# Sheet2.net
KiCad netlist of a schematic drawn in Altium Designer
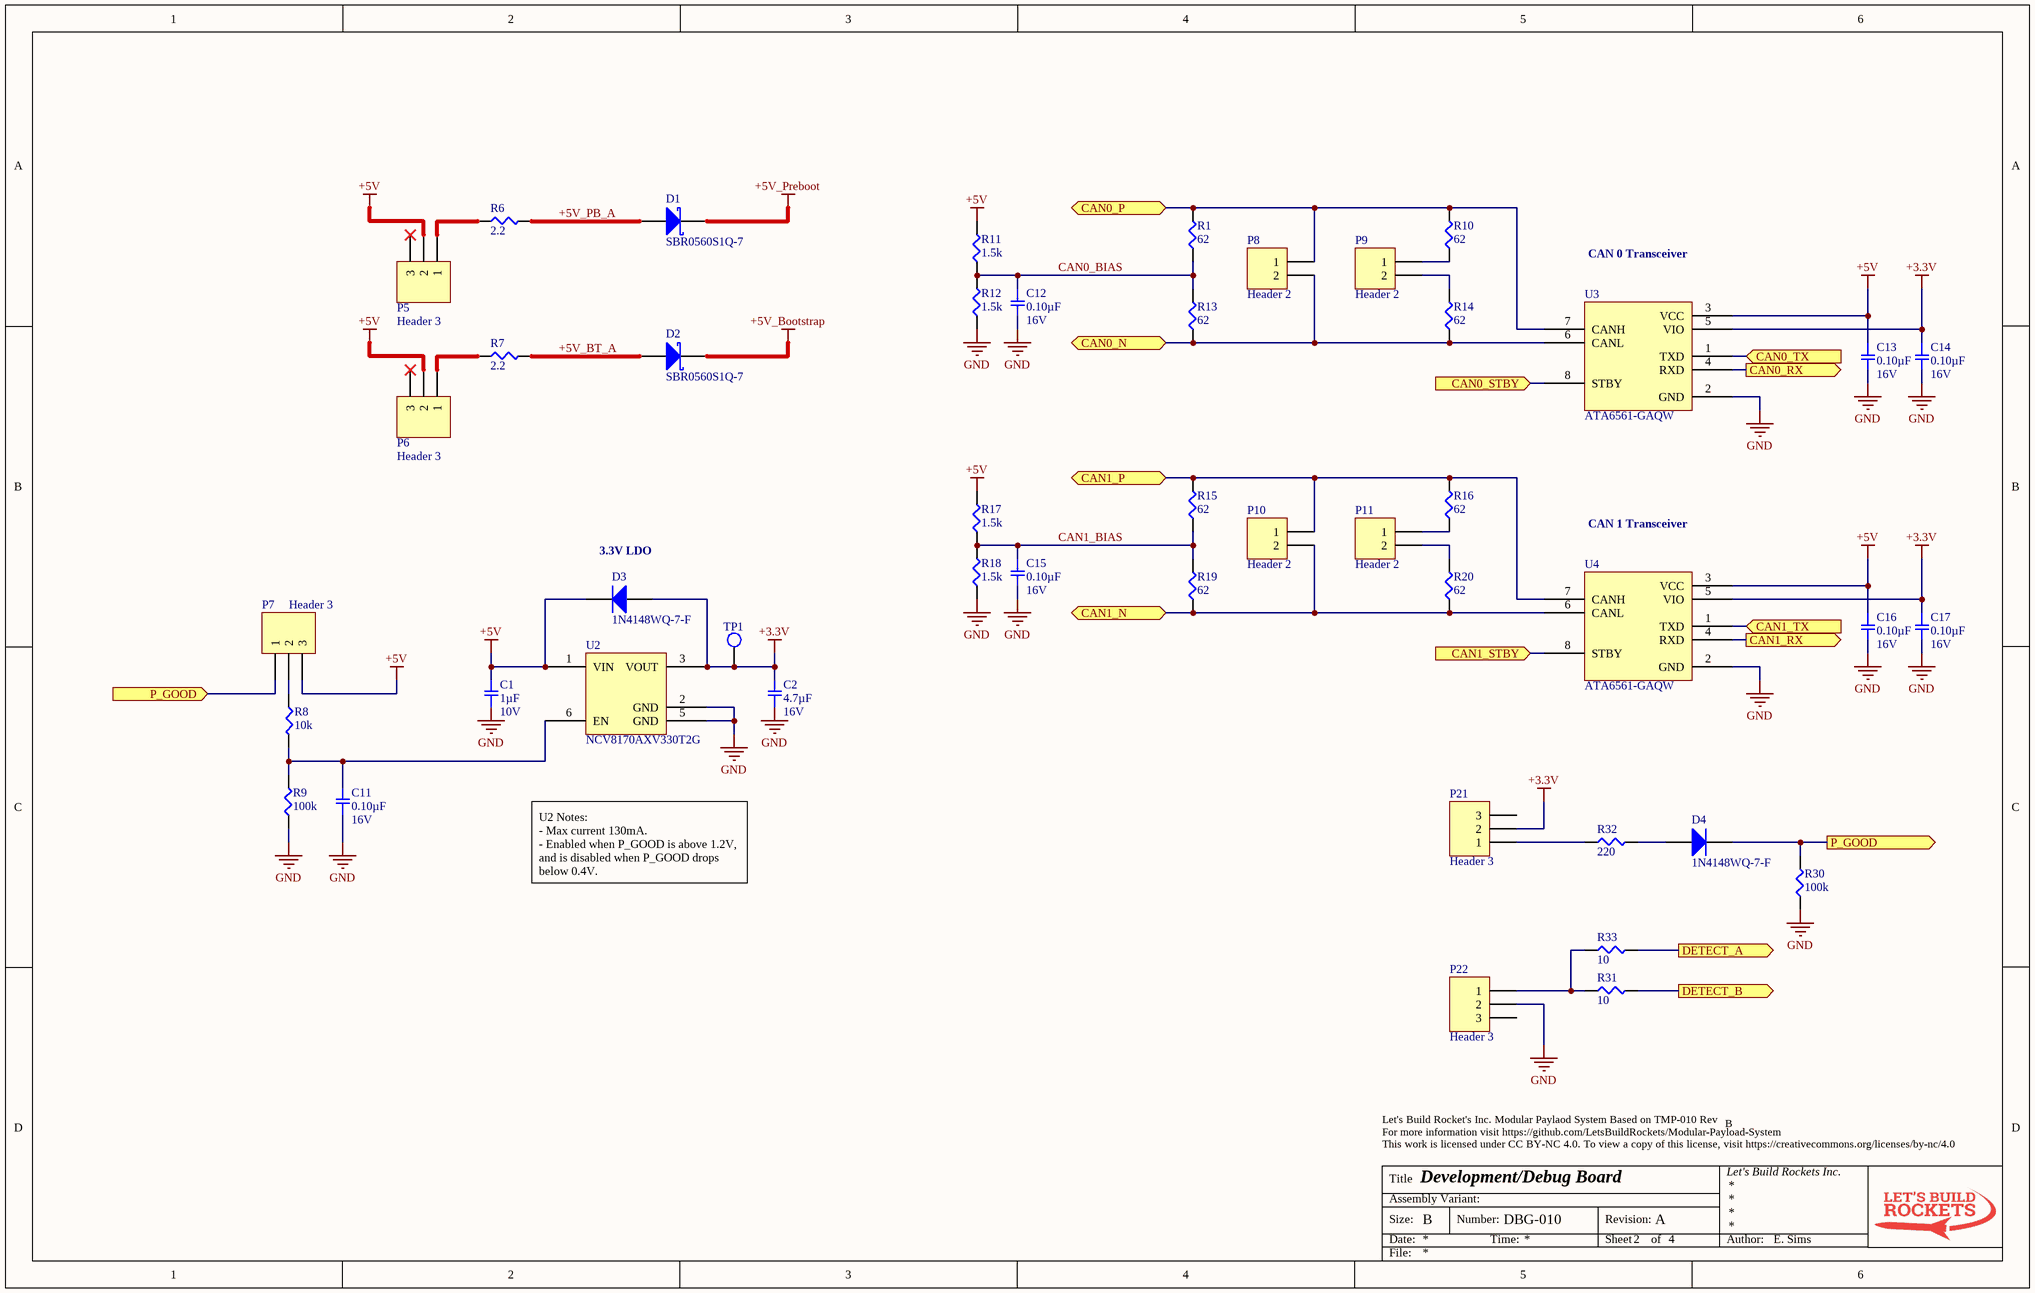
[diagram p0: Sheet2.SchDoc]

(export (version "E")
  (design (tool "Eeschema 10.0.6"))
  (components
    (comp (ref "C1")
      (value "1µF")
      (footprint "SMD-0402C")
      (description "CAP CER 1UF 10V X7S 0402")
      (fields
        (field (name "DIGI-KEY PART NUMBER") "490-13409-1-ND")
        (field (name "PART NUMBER") "GCM155C71A105KE38D")
        (field (name "VOLTAGE") "10V")
      )
      (libsource (lib "capacitor_murata_0402") (part "GCM155C71A105KE38D"))
    )
    (comp (ref "C2")
      (value "4.7µF")
      (footprint "SMD-0805C")
      (description "CAP CER 4.7UF 16V X7R 0805")
      (fields
        (field (name "DIGI-KEY PART NUMBER") "490-10557-1-ND")
        (field (name "PART NUMBER") "GCJ21BR71C475KA01L")
        (field (name "VOLTAGE") "16V")
      )
      (libsource (lib "capacitor_murata_0805") (part "GCJ21BR71C475KA01L"))
    )
    (comp (ref "C11")
      (value "0.10µF")
      (footprint "SMD-0402C")
      (description "CAP CER 0.1UF 16V X7R 0402")
      (fields
        (field (name "DIGI-KEY PART NUMBER") "490-4759-1-ND")
        (field (name "PART NUMBER") "GCM155R71C104KA55D")
        (field (name "VOLTAGE") "16V")
      )
      (libsource (lib "capacitor_murata_0402") (part "GCM155R71C104KA55D"))
    )
    (comp (ref "C12")
      (value "0.10µF")
      (footprint "SMD-0402C")
      (description "CAP CER 0.1UF 16V X7R 0402")
      (fields
        (field (name "DIGI-KEY PART NUMBER") "490-4759-1-ND")
        (field (name "PART NUMBER") "GCM155R71C104KA55D")
        (field (name "VOLTAGE") "16V")
      )
      (libsource (lib "capacitor_murata_0402") (part "GCM155R71C104KA55D"))
    )
    (comp (ref "C13")
      (value "0.10µF")
      (footprint "SMD-0402C")
      (description "CAP CER 0.1UF 16V X7R 0402")
      (fields
        (field (name "DIGI-KEY PART NUMBER") "490-4759-1-ND")
        (field (name "PART NUMBER") "GCM155R71C104KA55D")
        (field (name "VOLTAGE") "16V")
      )
      (libsource (lib "capacitor_murata_0402") (part "GCM155R71C104KA55D"))
    )
    (comp (ref "C14")
      (value "0.10µF")
      (footprint "SMD-0402C")
      (description "CAP CER 0.1UF 16V X7R 0402")
      (fields
        (field (name "DIGI-KEY PART NUMBER") "490-4759-1-ND")
        (field (name "PART NUMBER") "GCM155R71C104KA55D")
        (field (name "VOLTAGE") "16V")
      )
      (libsource (lib "capacitor_murata_0402") (part "GCM155R71C104KA55D"))
    )
    (comp (ref "C15")
      (value "0.10µF")
      (footprint "SMD-0402C")
      (description "CAP CER 0.1UF 16V X7R 0402")
      (fields
        (field (name "DIGI-KEY PART NUMBER") "490-4759-1-ND")
        (field (name "PART NUMBER") "GCM155R71C104KA55D")
        (field (name "VOLTAGE") "16V")
      )
      (libsource (lib "capacitor_murata_0402") (part "GCM155R71C104KA55D"))
    )
    (comp (ref "C16")
      (value "0.10µF")
      (footprint "SMD-0402C")
      (description "CAP CER 0.1UF 16V X7R 0402")
      (fields
        (field (name "DIGI-KEY PART NUMBER") "490-4759-1-ND")
        (field (name "PART NUMBER") "GCM155R71C104KA55D")
        (field (name "VOLTAGE") "16V")
      )
      (libsource (lib "capacitor_murata_0402") (part "GCM155R71C104KA55D"))
    )
    (comp (ref "C17")
      (value "0.10µF")
      (footprint "SMD-0402C")
      (description "CAP CER 0.1UF 16V X7R 0402")
      (fields
        (field (name "DIGI-KEY PART NUMBER") "490-4759-1-ND")
        (field (name "PART NUMBER") "GCM155R71C104KA55D")
        (field (name "VOLTAGE") "16V")
      )
      (libsource (lib "capacitor_murata_0402") (part "GCM155R71C104KA55D"))
    )
    (comp (ref "D1")
      (value "SBR0560S1Q-7")
      (footprint "SOD123")
      (libsource (lib "ModularPayload") (part "SBR0560S1Q-7"))
    )
    (comp (ref "D2")
      (value "SBR0560S1Q-7")
      (footprint "SOD123")
      (libsource (lib "ModularPayload") (part "SBR0560S1Q-7"))
    )
    (comp (ref "D3")
      (value "1N4148WQ-7-F")
      (footprint "SOD123")
      (libsource (lib "ModularPayload") (part "1N4148WQ-7-F"))
    )
    (comp (ref "D4")
      (value "1N4148WQ-7-F")
      (footprint "SOD123")
      (libsource (lib "ModularPayload") (part "1N4148WQ-7-F"))
    )
    (comp (ref "P5")
      (value "Header 3")
      (footprint "HDR1X3")
      (description "Header, 3-Pin")
      (fields (field (name "PUBLISHER") "Altium Limited"))
      (libsource (lib "Miscellaneous Connectors") (part "Header 3"))
    )
    (comp (ref "P6")
      (value "Header 3")
      (footprint "HDR1X3")
      (description "Header, 3-Pin")
      (fields (field (name "PUBLISHER") "Altium Limited"))
      (libsource (lib "Miscellaneous Connectors") (part "Header 3"))
    )
    (comp (ref "P7")
      (value "Header 3")
      (footprint "HDR1X3")
      (description "Header, 3-Pin")
      (fields (field (name "PUBLISHER") "Altium Limited"))
      (libsource (lib "") (part "Header 3_2"))
    )
    (comp (ref "P8")
      (value "Header 2")
      (footprint "HDR1X2")
      (description "Header, 2-Pin")
      (fields (field (name "PUBLISHER") "Altium Limited"))
      (libsource (lib "Miscellaneous Connectors") (part "Header 2"))
    )
    (comp (ref "P9")
      (value "Header 2")
      (footprint "HDR1X2")
      (description "Header, 2-Pin")
      (fields (field (name "PUBLISHER") "Altium Limited"))
      (libsource (lib "Miscellaneous Connectors") (part "Header 2"))
    )
    (comp (ref "P10")
      (value "Header 2")
      (footprint "HDR1X2")
      (description "Header, 2-Pin")
      (fields (field (name "PUBLISHER") "Altium Limited"))
      (libsource (lib "Miscellaneous Connectors") (part "Header 2"))
    )
    (comp (ref "P11")
      (value "Header 2")
      (footprint "HDR1X2")
      (description "Header, 2-Pin")
      (fields (field (name "PUBLISHER") "Altium Limited"))
      (libsource (lib "Miscellaneous Connectors") (part "Header 2"))
    )
    (comp (ref "P21")
      (value "Header 3")
      (footprint "HDR1X3")
      (description "Header, 3-Pin")
      (fields (field (name "PUBLISHER") "Altium Limited"))
      (libsource (lib "") (part "Header 3_1"))
    )
    (comp (ref "P22")
      (value "Header 3")
      (footprint "HDR1X3")
      (description "Header, 3-Pin")
      (fields (field (name "PUBLISHER") "Altium Limited"))
      (libsource (lib "Miscellaneous Connectors") (part "Header 3"))
    )
    (comp (ref "R1")
      (value "62")
      (footprint "SMD-0603-RES")
      (description "RES SMD 62 OHM 5% 1/4W 0603")
      (fields
        (field (name "PART NUMBER") "ERJ-PA3J620V")
        (field (name "DIGI-KEY PART NUMBER") "P62.00BZCT-ND")
      )
      (libsource (lib "Panasonic_ERJ_0603") (part "ERJ-PA3J620V"))
    )
    (comp (ref "R6")
      (value "2.2")
      (footprint "SMD-0805-RES")
      (description "RES SMD 2.2 OHM 5% 1/8W 0805")
      (fields (field (name "PART NUMBER") "ERJ-6GEYJ2R2V") (field (name "DIGI-KEY PART NUMBER") "P2.2ACT-ND"))
      (libsource (lib "Panasonic_ERJ_0805") (part "ERJ-6GEYJ2R2V"))
    )
    (comp (ref "R7")
      (value "2.2")
      (footprint "SMD-0805-RES")
      (description "RES SMD 2.2 OHM 5% 1/8W 0805")
      (fields (field (name "PART NUMBER") "ERJ-6GEYJ2R2V") (field (name "DIGI-KEY PART NUMBER") "P2.2ACT-ND"))
      (libsource (lib "Panasonic_ERJ_0805") (part "ERJ-6GEYJ2R2V"))
    )
    (comp (ref "R8")
      (value "10k")
      (footprint "SMD-0402-RES")
      (description "RES SMD 10K OHM 5% 1/10W 0402")
      (fields (field (name "PART NUMBER") "ERJ-2GEJ103X") (field (name "DIGI-KEY PART NUMBER") "P10KJCT-ND"))
      (libsource (lib "Panasonic_ERJ_0402") (part "ERJ-2GEJ103X"))
    )
    (comp (ref "R9")
      (value "100k")
      (footprint "SMD-0402-RES")
      (description "RES SMD 100K OHM 5% 1/10W 0402")
      (fields (field (name "PART NUMBER") "ERJ-2GEJ104X") (field (name "DIGI-KEY PART NUMBER") "P100KJCT-ND"))
      (libsource (lib "Panasonic_ERJ_0402") (part "ERJ-2GEJ104X"))
    )
    (comp (ref "R10")
      (value "62")
      (footprint "SMD-0603-RES")
      (description "RES SMD 62 OHM 5% 1/4W 0603")
      (fields
        (field (name "PART NUMBER") "ERJ-PA3J620V")
        (field (name "DIGI-KEY PART NUMBER") "P62.00BZCT-ND")
      )
      (libsource (lib "Panasonic_ERJ_0603") (part "ERJ-PA3J620V"))
    )
    (comp (ref "R11")
      (value "1.5k")
      (footprint "SMD-0402-RES")
      (description "RES SMD 1.5K OHM 1% 1/10W 0402")
      (fields
        (field (name "PART NUMBER") "ERJ-2RKF1501X")
        (field (name "DIGI-KEY PART NUMBER") "P1.50KLCT-ND")
      )
      (libsource (lib "Panasonic_ERJ_0402") (part "ERJ-2RKF1501X"))
    )
    (comp (ref "R12")
      (value "1.5k")
      (footprint "SMD-0402-RES")
      (description "RES SMD 1.5K OHM 1% 1/10W 0402")
      (fields
        (field (name "PART NUMBER") "ERJ-2RKF1501X")
        (field (name "DIGI-KEY PART NUMBER") "P1.50KLCT-ND")
      )
      (libsource (lib "Panasonic_ERJ_0402") (part "ERJ-2RKF1501X"))
    )
    (comp (ref "R13")
      (value "62")
      (footprint "SMD-0603-RES")
      (description "RES SMD 62 OHM 5% 1/4W 0603")
      (fields
        (field (name "PART NUMBER") "ERJ-PA3J620V")
        (field (name "DIGI-KEY PART NUMBER") "P62.00BZCT-ND")
      )
      (libsource (lib "Panasonic_ERJ_0603") (part "ERJ-PA3J620V"))
    )
    (comp (ref "R14")
      (value "62")
      (footprint "SMD-0603-RES")
      (description "RES SMD 62 OHM 5% 1/4W 0603")
      (fields
        (field (name "PART NUMBER") "ERJ-PA3J620V")
        (field (name "DIGI-KEY PART NUMBER") "P62.00BZCT-ND")
      )
      (libsource (lib "Panasonic_ERJ_0603") (part "ERJ-PA3J620V"))
    )
    (comp (ref "R15")
      (value "62")
      (footprint "SMD-0603-RES")
      (description "RES SMD 62 OHM 5% 1/4W 0603")
      (fields
        (field (name "PART NUMBER") "ERJ-PA3J620V")
        (field (name "DIGI-KEY PART NUMBER") "P62.00BZCT-ND")
      )
      (libsource (lib "Panasonic_ERJ_0603") (part "ERJ-PA3J620V"))
    )
    (comp (ref "R16")
      (value "62")
      (footprint "SMD-0603-RES")
      (description "RES SMD 62 OHM 5% 1/4W 0603")
      (fields
        (field (name "PART NUMBER") "ERJ-PA3J620V")
        (field (name "DIGI-KEY PART NUMBER") "P62.00BZCT-ND")
      )
      (libsource (lib "Panasonic_ERJ_0603") (part "ERJ-PA3J620V"))
    )
    (comp (ref "R17")
      (value "1.5k")
      (footprint "SMD-0402-RES")
      (description "RES SMD 1.5K OHM 1% 1/10W 0402")
      (fields
        (field (name "PART NUMBER") "ERJ-2RKF1501X")
        (field (name "DIGI-KEY PART NUMBER") "P1.50KLCT-ND")
      )
      (libsource (lib "Panasonic_ERJ_0402") (part "ERJ-2RKF1501X"))
    )
    (comp (ref "R18")
      (value "1.5k")
      (footprint "SMD-0402-RES")
      (description "RES SMD 1.5K OHM 1% 1/10W 0402")
      (fields
        (field (name "PART NUMBER") "ERJ-2RKF1501X")
        (field (name "DIGI-KEY PART NUMBER") "P1.50KLCT-ND")
      )
      (libsource (lib "Panasonic_ERJ_0402") (part "ERJ-2RKF1501X"))
    )
    (comp (ref "R19")
      (value "62")
      (footprint "SMD-0603-RES")
      (description "RES SMD 62 OHM 5% 1/4W 0603")
      (fields
        (field (name "PART NUMBER") "ERJ-PA3J620V")
        (field (name "DIGI-KEY PART NUMBER") "P62.00BZCT-ND")
      )
      (libsource (lib "Panasonic_ERJ_0603") (part "ERJ-PA3J620V"))
    )
    (comp (ref "R20")
      (value "62")
      (footprint "SMD-0603-RES")
      (description "RES SMD 62 OHM 5% 1/4W 0603")
      (fields
        (field (name "PART NUMBER") "ERJ-PA3J620V")
        (field (name "DIGI-KEY PART NUMBER") "P62.00BZCT-ND")
      )
      (libsource (lib "Panasonic_ERJ_0603") (part "ERJ-PA3J620V"))
    )
    (comp (ref "R30")
      (value "100k")
      (footprint "SMD-0402-RES")
      (description "RES SMD 100K OHM 5% 1/10W 0402")
      (fields (field (name "PART NUMBER") "ERJ-2GEJ104X") (field (name "DIGI-KEY PART NUMBER") "P100KJCT-ND"))
      (libsource (lib "Panasonic_ERJ_0402") (part "ERJ-2GEJ104X"))
    )
    (comp (ref "R31")
      (value "10")
      (footprint "SMD-0402-RES")
      (description "RES SMD 10 OHM 5% 1/10W 0402")
      (fields (field (name "PART NUMBER") "ERJ-2GEJ100X") (field (name "DIGI-KEY PART NUMBER") "P10JCT-ND"))
      (libsource (lib "Panasonic_ERJ_0402") (part "ERJ-2GEJ100X"))
    )
    (comp (ref "R32")
      (value "220")
      (footprint "SMD-0402-RES")
      (description "RES SMD 220 OHM 5% 1/10W 0402")
      (fields (field (name "PART NUMBER") "ERJ-2GEJ221X") (field (name "DIGI-KEY PART NUMBER") "P220JCT-ND"))
      (libsource (lib "Panasonic_ERJ_0402") (part "ERJ-2GEJ221X"))
    )
    (comp (ref "R33")
      (value "10")
      (footprint "SMD-0402-RES")
      (description "RES SMD 10 OHM 5% 1/10W 0402")
      (fields (field (name "PART NUMBER") "ERJ-2GEJ100X") (field (name "DIGI-KEY PART NUMBER") "P10JCT-ND"))
      (libsource (lib "Panasonic_ERJ_0402") (part "ERJ-2GEJ100X"))
    )
    (comp (ref "TP1") (value "TP") (footprint "TP_SMD_40") (libsource (lib "TP") (part "TP")))
    (comp (ref "U2")
      (value "NCV8170AXV330T2G")
      (footprint "SOTFL50P160X60-6N")
      (libsource (lib "ModularPayload") (part "NCV8170AXV330T2G"))
    )
    (comp (ref "U3")
      (value "ATA6561-GAQW")
      (footprint "SOIC127P600X175-8N")
      (libsource (lib "ModularPayload") (part "ATA6561-GAQW"))
    )
    (comp (ref "U4")
      (value "ATA6561-GAQW")
      (footprint "SOIC127P600X175-8N")
      (libsource (lib "ModularPayload") (part "ATA6561-GAQW"))
    )
  )
  (nets
    (net (code "1") (name "+3.3V") (class "Default")
      (node (ref "C14") (pin "1") (pinfunction "1_1") (pintype "passive"))
      (node (ref "C17") (pin "1") (pinfunction "1_1") (pintype "passive"))
      (node (ref "C2") (pin "2") (pinfunction "2_2") (pintype "passive"))
      (node (ref "D3") (pin "A") (pinfunction "A_A") (pintype "passive"))
      (node (ref "P21") (pin "2") (pinfunction "2_2") (pintype "passive"))
      (node (ref "TP1") (pin "1") (pintype "passive"))
      (node (ref "U2") (pin "3") (pinfunction "VOUT_3") (pintype "passive"))
      (node (ref "U3") (pin "5") (pinfunction "VIO_5") (pintype "passive"))
      (node (ref "U4") (pin "5") (pinfunction "VIO_5") (pintype "passive"))
    )
    (net (code "2") (name "+5V") (class "Default")
      (node (ref "C1") (pin "2") (pinfunction "2_2") (pintype "passive"))
      (node (ref "C13") (pin "1") (pinfunction "1_1") (pintype "passive"))
      (node (ref "C16") (pin "1") (pinfunction "1_1") (pintype "passive"))
      (node (ref "D3") (pin "K") (pinfunction "K_K") (pintype "passive"))
      (node (ref "P5") (pin "2") (pinfunction "2_2") (pintype "passive"))
      (node (ref "P6") (pin "2") (pinfunction "2_2") (pintype "passive"))
      (node (ref "P7") (pin "3") (pinfunction "3_3") (pintype "passive"))
      (node (ref "R11") (pin "2") (pinfunction "2_2") (pintype "passive"))
      (node (ref "R17") (pin "2") (pinfunction "2_2") (pintype "passive"))
      (node (ref "U2") (pin "1") (pinfunction "VIN_1") (pintype "passive"))
      (node (ref "U3") (pin "3") (pinfunction "VCC_3") (pintype "passive"))
      (node (ref "U4") (pin "3") (pinfunction "VCC_3") (pintype "passive"))
    )
    (net (code "3") (name "+5V_Bootstrap") (class "Default")
      (node (ref "D2") (pin "K") (pinfunction "K_K") (pintype "passive"))
    )
    (net (code "4") (name "+5V_Preboot") (class "Default")
      (node (ref "D1") (pin "K") (pinfunction "K_K") (pintype "passive"))
    )
    (net (code "5") (name "/+5V_BT_A") (class "Default")
      (node (ref "D2") (pin "A") (pinfunction "A_A") (pintype "passive"))
      (node (ref "R7") (pin "2") (pinfunction "2_2") (pintype "passive"))
    )
    (net (code "6") (name "/+5V_PB_A") (class "Default")
      (node (ref "D1") (pin "A") (pinfunction "A_A") (pintype "passive"))
      (node (ref "R6") (pin "2") (pinfunction "2_2") (pintype "passive"))
    )
    (net (code "7") (name "/CAN0_BIAS") (class "Default")
      (node (ref "C12") (pin "1") (pinfunction "1_1") (pintype "passive"))
      (node (ref "R1") (pin "1") (pinfunction "1_1") (pintype "passive"))
      (node (ref "R11") (pin "1") (pinfunction "1_1") (pintype "passive"))
      (node (ref "R12") (pin "2") (pinfunction "2_2") (pintype "passive"))
      (node (ref "R13") (pin "2") (pinfunction "2_2") (pintype "passive"))
    )
    (net (code "8") (name "/CAN0_N") (class "Default")
      (node (ref "P8") (pin "2") (pinfunction "2_2") (pintype "passive"))
      (node (ref "R13") (pin "1") (pinfunction "1_1") (pintype "passive"))
      (node (ref "R14") (pin "1") (pinfunction "1_1") (pintype "passive"))
      (node (ref "U3") (pin "6") (pinfunction "CANL_6") (pintype "passive"))
    )
    (net (code "9") (name "/CAN0_P") (class "Default")
      (node (ref "P8") (pin "1") (pinfunction "1_1") (pintype "passive"))
      (node (ref "R1") (pin "2") (pinfunction "2_2") (pintype "passive"))
      (node (ref "R10") (pin "2") (pinfunction "2_2") (pintype "passive"))
      (node (ref "U3") (pin "7") (pinfunction "CANH_7") (pintype "passive"))
    )
    (net (code "10") (name "/CAN0_RX") (class "Default")
      (node (ref "U3") (pin "4") (pinfunction "RXD_4") (pintype "passive"))
    )
    (net (code "11") (name "/CAN0_STBY") (class "Default")
      (node (ref "U3") (pin "8") (pinfunction "STBY_8") (pintype "passive"))
    )
    (net (code "12") (name "/CAN0_TX") (class "Default")
      (node (ref "U3") (pin "1") (pinfunction "TXD_1") (pintype "passive"))
    )
    (net (code "13") (name "/CAN1_BIAS") (class "Default")
      (node (ref "C15") (pin "1") (pinfunction "1_1") (pintype "passive"))
      (node (ref "R15") (pin "1") (pinfunction "1_1") (pintype "passive"))
      (node (ref "R17") (pin "1") (pinfunction "1_1") (pintype "passive"))
      (node (ref "R18") (pin "2") (pinfunction "2_2") (pintype "passive"))
      (node (ref "R19") (pin "2") (pinfunction "2_2") (pintype "passive"))
    )
    (net (code "14") (name "/CAN1_N") (class "Default")
      (node (ref "P10") (pin "2") (pinfunction "2_2") (pintype "passive"))
      (node (ref "R19") (pin "1") (pinfunction "1_1") (pintype "passive"))
      (node (ref "R20") (pin "1") (pinfunction "1_1") (pintype "passive"))
      (node (ref "U4") (pin "6") (pinfunction "CANL_6") (pintype "passive"))
    )
    (net (code "15") (name "/CAN1_P") (class "Default")
      (node (ref "P10") (pin "1") (pinfunction "1_1") (pintype "passive"))
      (node (ref "R15") (pin "2") (pinfunction "2_2") (pintype "passive"))
      (node (ref "R16") (pin "2") (pinfunction "2_2") (pintype "passive"))
      (node (ref "U4") (pin "7") (pinfunction "CANH_7") (pintype "passive"))
    )
    (net (code "16") (name "/CAN1_RX") (class "Default")
      (node (ref "U4") (pin "4") (pinfunction "RXD_4") (pintype "passive"))
    )
    (net (code "17") (name "/CAN1_STBY") (class "Default")
      (node (ref "U4") (pin "8") (pinfunction "STBY_8") (pintype "passive"))
    )
    (net (code "18") (name "/CAN1_TX") (class "Default")
      (node (ref "U4") (pin "1") (pinfunction "TXD_1") (pintype "passive"))
    )
    (net (code "19") (name "/DETECT_A") (class "Default")
      (node (ref "R33") (pin "2") (pinfunction "2_2") (pintype "passive"))
    )
    (net (code "20") (name "/DETECT_B") (class "Default")
      (node (ref "R31") (pin "2") (pinfunction "2_2") (pintype "passive"))
    )
    (net (code "21") (name "/P_GOOD") (class "Default")
      (node (ref "D4") (pin "K") (pinfunction "K_K") (pintype "passive"))
      (node (ref "P7") (pin "1") (pinfunction "1_1") (pintype "passive"))
      (node (ref "R30") (pin "2") (pinfunction "2_2") (pintype "passive"))
    )
    (net (code "22") (name "GND") (class "Default")
      (node (ref "C1") (pin "1") (pinfunction "1_1") (pintype "passive"))
      (node (ref "C11") (pin "1") (pinfunction "1_1") (pintype "passive"))
      (node (ref "C12") (pin "2") (pinfunction "2_2") (pintype "passive"))
      (node (ref "C13") (pin "2") (pinfunction "2_2") (pintype "passive"))
      (node (ref "C14") (pin "2") (pinfunction "2_2") (pintype "passive"))
      (node (ref "C15") (pin "2") (pinfunction "2_2") (pintype "passive"))
      (node (ref "C16") (pin "2") (pinfunction "2_2") (pintype "passive"))
      (node (ref "C17") (pin "2") (pinfunction "2_2") (pintype "passive"))
      (node (ref "C2") (pin "1") (pinfunction "1_1") (pintype "passive"))
      (node (ref "P22") (pin "2") (pinfunction "2_2") (pintype "passive"))
      (node (ref "R12") (pin "1") (pinfunction "1_1") (pintype "passive"))
      (node (ref "R18") (pin "1") (pinfunction "1_1") (pintype "passive"))
      (node (ref "R30") (pin "1") (pinfunction "1_1") (pintype "passive"))
      (node (ref "R9") (pin "1") (pinfunction "1_1") (pintype "passive"))
      (node (ref "U2") (pin "2") (pinfunction "GND_2") (pintype "passive"))
      (node (ref "U2") (pin "5") (pinfunction "GND_5") (pintype "passive"))
      (node (ref "U3") (pin "2") (pinfunction "GND_2") (pintype "passive"))
      (node (ref "U4") (pin "2") (pinfunction "GND_2") (pintype "passive"))
    )
    (net (code "23") (name "Net-(D4-PadA)") (class "Default")
      (node (ref "D4") (pin "A") (pinfunction "A_A") (pintype "passive"))
      (node (ref "R32") (pin "2") (pinfunction "2_2") (pintype "passive"))
    )
    (net (code "24") (name "Net-(P5-Pad1)") (class "Default")
      (node (ref "P5") (pin "1") (pinfunction "1_1") (pintype "passive"))
      (node (ref "R6") (pin "1") (pinfunction "1_1") (pintype "passive"))
    )
    (net (code "25") (name "Net-(P6-Pad1)") (class "Default")
      (node (ref "P6") (pin "1") (pinfunction "1_1") (pintype "passive"))
      (node (ref "R7") (pin "1") (pinfunction "1_1") (pintype "passive"))
    )
    (net (code "26") (name "Net-(P7-Pad2)") (class "Default")
      (node (ref "P7") (pin "2") (pinfunction "2_2") (pintype "passive"))
      (node (ref "R8") (pin "1") (pinfunction "1_1") (pintype "passive"))
    )
    (net (code "27") (name "Net-(P9-Pad1)") (class "Default")
      (node (ref "P9") (pin "1") (pinfunction "1_1") (pintype "passive"))
      (node (ref "R10") (pin "1") (pinfunction "1_1") (pintype "passive"))
    )
    (net (code "28") (name "Net-(P9-Pad2)") (class "Default")
      (node (ref "P9") (pin "2") (pinfunction "2_2") (pintype "passive"))
      (node (ref "R14") (pin "2") (pinfunction "2_2") (pintype "passive"))
    )
    (net (code "29") (name "Net-(P11-Pad1)") (class "Default")
      (node (ref "P11") (pin "1") (pinfunction "1_1") (pintype "passive"))
      (node (ref "R16") (pin "1") (pinfunction "1_1") (pintype "passive"))
    )
    (net (code "30") (name "Net-(P11-Pad2)") (class "Default")
      (node (ref "P11") (pin "2") (pinfunction "2_2") (pintype "passive"))
      (node (ref "R20") (pin "2") (pinfunction "2_2") (pintype "passive"))
    )
    (net (code "31") (name "Net-(P21-Pad1)") (class "Default")
      (node (ref "P21") (pin "1") (pinfunction "1_1") (pintype "passive"))
      (node (ref "R32") (pin "1") (pinfunction "1_1") (pintype "passive"))
    )
    (net (code "32") (name "Net-(P22-Pad1)") (class "Default")
      (node (ref "P22") (pin "1") (pinfunction "1_1") (pintype "passive"))
      (node (ref "R31") (pin "1") (pinfunction "1_1") (pintype "passive"))
      (node (ref "R33") (pin "1") (pinfunction "1_1") (pintype "passive"))
    )
    (net (code "33") (name "Net-(U2-EN)") (class "Default")
      (node (ref "C11") (pin "2") (pinfunction "2_2") (pintype "passive"))
      (node (ref "R8") (pin "2") (pinfunction "2_2") (pintype "passive"))
      (node (ref "R9") (pin "2") (pinfunction "2_2") (pintype "passive"))
      (node (ref "U2") (pin "6") (pinfunction "EN_6") (pintype "passive"))
    )
    (net (code "34") (name "unconnected-(P5-Pad3)") (class "Default")
      (node (ref "P5") (pin "3") (pinfunction "3_3") (pintype "passive+no_connect"))
    )
    (net (code "35") (name "unconnected-(P6-Pad3)") (class "Default")
      (node (ref "P6") (pin "3") (pinfunction "3_3") (pintype "passive+no_connect"))
    )
    (net (code "36") (name "unconnected-(P21-Pad3)") (class "Default")
      (node (ref "P21") (pin "3") (pinfunction "3_3") (pintype "passive"))
    )
    (net (code "37") (name "unconnected-(P22-Pad3)") (class "Default")
      (node (ref "P22") (pin "3") (pinfunction "3_3") (pintype "passive"))
    )
  )
)
